# vcsample.net
KiCad netlist of a schematic drawn in Altium Designer
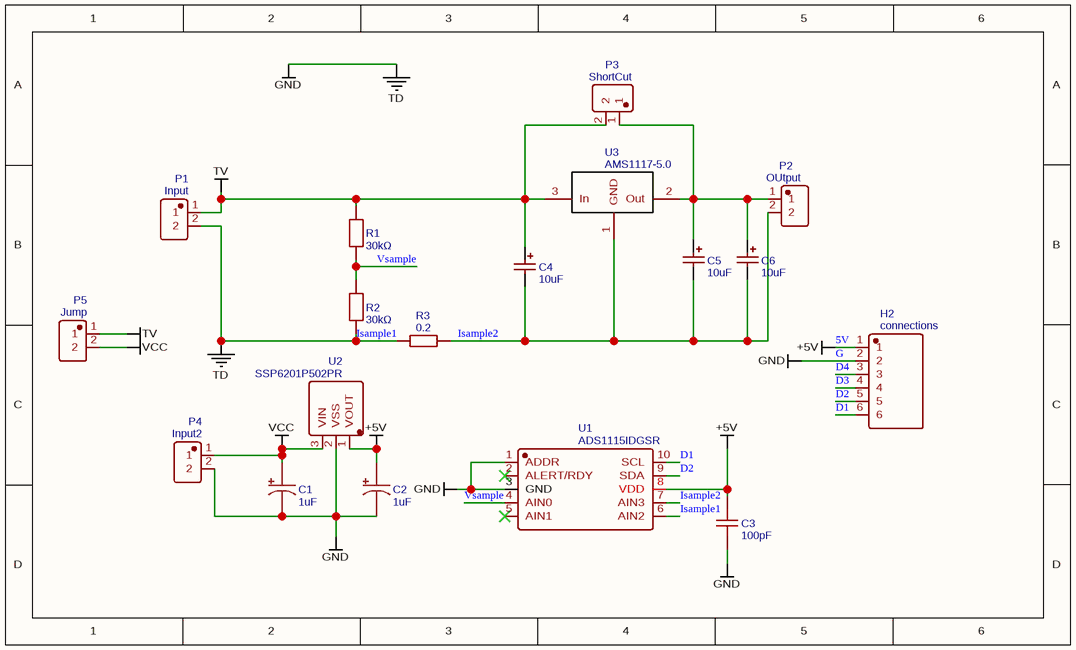
[diagram p0: vcsample.schdoc]

(export (version "E")
  (design (tool "Eeschema 10.0.6"))
  (components
    (comp (ref "C1")
      (value "1uF")
      (fields
        (field (name "BOM_MANUFACTURER PART") "TC212A105K025Y")
        (field (name "BOM_SUPPLIER PART") "C165110")
        (field (name "CONTRIBUTOR") "LCSC")
      )
      (libsource (lib "altium-import") (part "root_1_1uF_"))
    )
    (comp (ref "C2")
      (value "1uF")
      (fields
        (field (name "BOM_MANUFACTURER PART") "TC212A105K025Y")
        (field (name "BOM_SUPPLIER PART") "C165110")
        (field (name "CONTRIBUTOR") "LCSC")
      )
      (libsource (lib "altium-import") (part "root_1_1uF_"))
    )
    (comp (ref "C3")
      (value "100pF")
      (fields
        (field (name "BOM_SUPPLIER PART") "C526991")
        (field (name "BOM_MANUFACTURER PART") "CC0402JRNPO7BN101")
        (field (name "CONTRIBUTOR") "LCSC")
      )
      (libsource (lib "altium-import") (part "root_3_100pF_"))
    )
    (comp (ref "C4")
      (value "10uF")
      (fields
        (field (name "BOM_MANUFACTURER PART") "TAJB106K020RNJ")
        (field (name "BOM_SUPPLIER PART") "C8017")
      )
      (libsource (lib "altium-import") (part "root_1_10uF_"))
    )
    (comp (ref "C5")
      (value "10uF")
      (fields
        (field (name "BOM_MANUFACTURER PART") "TAJB106K020RNJ")
        (field (name "BOM_SUPPLIER PART") "C8017")
      )
      (libsource (lib "altium-import") (part "root_1_10uF_"))
    )
    (comp (ref "C6")
      (value "10uF")
      (fields
        (field (name "BOM_MANUFACTURER PART") "TAJB106K020RNJ")
        (field (name "BOM_SUPPLIER PART") "C8017")
      )
      (libsource (lib "altium-import") (part "root_1_10uF_"))
    )
    (comp (ref "H2")
      (value "connections")
      (fields
        (field (name "BOM_SUPPLIER PART") "C225492")
        (field (name "BOM_MANUFACTURER PART") "A2541WR-6P")
        (field (name "CONTRIBUTOR") "LCSC")
      )
      (libsource (lib "altium-import") (part "root_0_connections_"))
    )
    (comp (ref "P1")
      (value "Input")
      (fields
        (field (name "BOM_MANUFACTURER PART") "Female header1*2P")
        (field (name "BOM_SUPPLIER PART") "C66509")
      )
      (libsource (lib "altium-import") (part "root_0_Input_"))
    )
    (comp (ref "P2")
      (value "OUtput")
      (fields
        (field (name "BOM_MANUFACTURER PART") "Female header1*2P")
        (field (name "BOM_SUPPLIER PART") "C66509")
      )
      (libsource (lib "altium-import") (part "root_0_OUtput_"))
    )
    (comp (ref "P3")
      (value "ShortCut")
      (fields
        (field (name "BOM_MANUFACTURER PART") "Female header1*2P")
        (field (name "BOM_SUPPLIER PART") "C66509")
      )
      (libsource (lib "altium-import") (part "root_3_ShortCut_"))
    )
    (comp (ref "P4")
      (value "Input2")
      (fields
        (field (name "BOM_MANUFACTURER PART") "Female header1*2P")
        (field (name "BOM_SUPPLIER PART") "C66509")
      )
      (libsource (lib "altium-import") (part "root_0_Input2_"))
    )
    (comp (ref "P5")
      (value "Jump")
      (fields
        (field (name "BOM_MANUFACTURER PART") "Female header1*2P")
        (field (name "BOM_SUPPLIER PART") "C66509")
      )
      (libsource (lib "altium-import") (part "root_0_Jump_"))
    )
    (comp (ref "R1")
      (value "30kΩ")
      (fields
        (field (name "BOM_SUPPLIER PART") "C517551")
        (field (name "BOM_MANUFACTURER PART") "TC0550B3002T5J")
        (field (name "CONTRIBUTOR") "LCSC")
      )
      (libsource (lib "altium-import") (part "root_3_30kΩ_"))
    )
    (comp (ref "R2")
      (value "30kΩ")
      (fields
        (field (name "BOM_SUPPLIER PART") "C517551")
        (field (name "BOM_MANUFACTURER PART") "TC0550B3002T5J")
        (field (name "CONTRIBUTOR") "LCSC")
      )
      (libsource (lib "altium-import") (part "root_3_30kΩ_"))
    )
    (comp (ref "R3")
      (value "0.2")
      (fields
        (field (name "BOM_SUPPLIER PART") "C270925")
        (field (name "BOM_MANUFACTURER PART") "0805W4F200LT5E")
        (field (name "CONTRIBUTOR") "LCSC")
      )
      (libsource (lib "altium-import") (part "root_0_0.2_"))
    )
    (comp (ref "U1")
      (value "ADS1115IDGSR")
      (fields (field (name "BOM_SUPPLIER PART") "C37593"))
      (libsource (lib "altium-import") (part "root_0_ADS1115IDGSR_"))
    )
    (comp (ref "U2")
      (value "SSP6201P502PR")
      (fields (field (name "BOM_SUPPLIER PART") "C330932") (field (name "CONTRIBUTOR") "LCSC"))
      (libsource (lib "altium-import") (part "root_0_SSP6201P502PR_"))
    )
    (comp (ref "U3")
      (value "AMS1117-5.0")
      (fields (field (name "BOM_SUPPLIER PART") "C6187"))
      (libsource (lib "altium-import") (part "root_0_AMS1117-5.0_"))
    )
  )
  (nets
    (net (code "1") (name "+5V") (class "Default")
      (node (ref "C2") (pin "1") (pinfunction "1_1") (pintype "passive"))
      (node (ref "C3") (pin "1") (pinfunction "1_1") (pintype "passive"))
      (node (ref "H2") (pin "1") (pinfunction "1_1") (pintype "passive"))
      (node (ref "U1") (pin "8") (pinfunction "VDD_8") (pintype "passive"))
      (node (ref "U2") (pin "1") (pinfunction "VOUT_1") (pintype "passive"))
    )
    (net (code "2") (name "/D1") (class "Default")
      (node (ref "H2") (pin "6") (pinfunction "6_6") (pintype "passive"))
      (node (ref "U1") (pin "10") (pinfunction "SCL_10") (pintype "passive"))
    )
    (net (code "3") (name "/D2") (class "Default")
      (node (ref "H2") (pin "5") (pinfunction "5_5") (pintype "passive"))
      (node (ref "U1") (pin "9") (pinfunction "SDA_9") (pintype "passive"))
    )
    (net (code "4") (name "/D3") (class "Default")
      (node (ref "H2") (pin "4") (pinfunction "4_4") (pintype "passive"))
    )
    (net (code "5") (name "/D4") (class "Default")
      (node (ref "H2") (pin "3") (pinfunction "3_3") (pintype "passive"))
    )
    (net (code "6") (name "/Isample2") (class "Default")
      (node (ref "C4") (pin "2") (pinfunction "2_2") (pintype "passive"))
      (node (ref "C5") (pin "2") (pinfunction "2_2") (pintype "passive"))
      (node (ref "C6") (pin "2") (pinfunction "2_2") (pintype "passive"))
      (node (ref "P2") (pin "2") (pinfunction "2_2") (pintype "passive"))
      (node (ref "R3") (pin "2") (pinfunction "2_2") (pintype "passive"))
      (node (ref "U1") (pin "7") (pinfunction "AIN3_7") (pintype "passive"))
      (node (ref "U3") (pin "1") (pinfunction "GND_1") (pintype "passive"))
    )
    (net (code "7") (name "/Vsample") (class "Default")
      (node (ref "R1") (pin "2") (pinfunction "2_2") (pintype "passive"))
      (node (ref "R2") (pin "1") (pinfunction "1_1") (pintype "passive"))
      (node (ref "U1") (pin "4") (pinfunction "AIN0_4") (pintype "passive"))
    )
    (net (code "8") (name "GND") (class "Default")
      (node (ref "C1") (pin "2") (pinfunction "2_2") (pintype "passive"))
      (node (ref "C2") (pin "2") (pinfunction "2_2") (pintype "passive"))
      (node (ref "C3") (pin "2") (pinfunction "2_2") (pintype "passive"))
      (node (ref "H2") (pin "2") (pinfunction "2_2") (pintype "passive"))
      (node (ref "P1") (pin "2") (pinfunction "2_2") (pintype "passive"))
      (node (ref "P4") (pin "2") (pinfunction "2_2") (pintype "passive"))
      (node (ref "R2") (pin "2") (pinfunction "2_2") (pintype "passive"))
      (node (ref "R3") (pin "1") (pinfunction "1_1") (pintype "passive"))
      (node (ref "U1") (pin "1") (pinfunction "ADDR_1") (pintype "passive"))
      (node (ref "U1") (pin "3") (pinfunction "GND_3") (pintype "passive"))
      (node (ref "U1") (pin "6") (pinfunction "AIN2_6") (pintype "passive"))
      (node (ref "U2") (pin "2") (pinfunction "VSS_2") (pintype "passive"))
    )
    (net (code "9") (name "Net-(U3-Out)") (class "Default")
      (node (ref "C5") (pin "1") (pinfunction "1_1") (pintype "passive"))
      (node (ref "C6") (pin "1") (pinfunction "1_1") (pintype "passive"))
      (node (ref "P2") (pin "1") (pinfunction "1_1") (pintype "passive"))
      (node (ref "P3") (pin "1") (pinfunction "1_1") (pintype "passive"))
      (node (ref "U3") (pin "2") (pinfunction "Out_2") (pintype "passive"))
    )
    (net (code "10") (name "TV") (class "Default")
      (node (ref "C4") (pin "1") (pinfunction "1_1") (pintype "passive"))
      (node (ref "P1") (pin "1") (pinfunction "1_1") (pintype "passive"))
      (node (ref "P3") (pin "2") (pinfunction "2_2") (pintype "passive"))
      (node (ref "P5") (pin "1") (pinfunction "1_1") (pintype "passive"))
      (node (ref "R1") (pin "1") (pinfunction "1_1") (pintype "passive"))
      (node (ref "U3") (pin "3") (pinfunction "In_3") (pintype "passive"))
    )
    (net (code "11") (name "VCC") (class "Default")
      (node (ref "C1") (pin "1") (pinfunction "1_1") (pintype "passive"))
      (node (ref "P4") (pin "1") (pinfunction "1_1") (pintype "passive"))
      (node (ref "P5") (pin "2") (pinfunction "2_2") (pintype "passive"))
      (node (ref "U2") (pin "3") (pinfunction "VIN_3") (pintype "passive"))
    )
    (net (code "12") (name "unconnected-(U1-AIN1-Pad5)") (class "Default")
      (node (ref "U1") (pin "5") (pinfunction "AIN1_5") (pintype "passive+no_connect"))
    )
    (net (code "13") (name "unconnected-(U1-ALERT{slash}RDY-Pad2)") (class "Default")
      (node (ref "U1") (pin "2") (pinfunction "ALERT/RDY_2") (pintype "passive+no_connect"))
    )
  )
)
